# 4-USB-A.net
KiCad netlist of a schematic drawn in Altium Designer
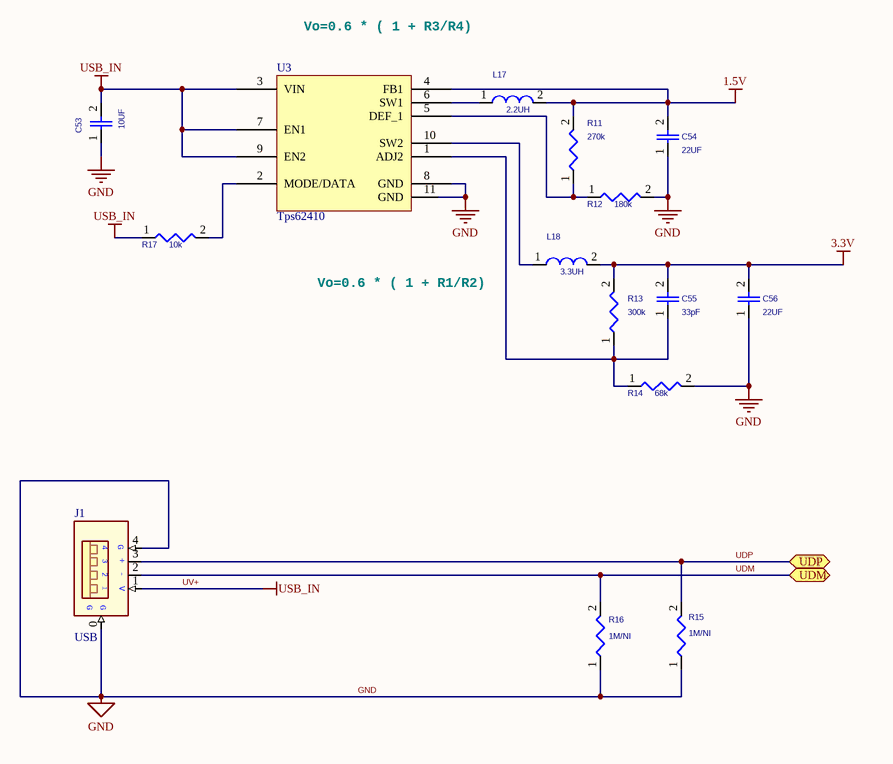
[diagram p0: 4-USB-A.SchDoc]

(export (version "E")
  (design (tool "Eeschema 10.0.6"))
  (components
    (comp (ref "C53") (value "10UF") (footprint "0805") (libsource (lib "*") (part "CAP/0402")))
    (comp (ref "C54") (value "22UF") (footprint "0805") (libsource (lib "*") (part "CAP/0402")))
    (comp (ref "C55") (value "33pF") (footprint "0402") (libsource (lib "*") (part "CAP/0402")))
    (comp (ref "C56") (value "22UF") (footprint "0805") (libsource (lib "*") (part "CAP/0402")))
    (comp (ref "J1") (value "USB") (footprint "USB-A-MALE") (libsource (lib "Euler") (part "USB")))
    (comp (ref "L17") (value "2.2UH") (footprint "0806") (libsource (lib "*") (part "L/2.5*2.0")))
    (comp (ref "L18") (value "3.3UH") (footprint "0806") (libsource (lib "*") (part "L/2.5*2.0")))
    (comp (ref "R11") (value "270k") (footprint "0402") (libsource (lib "*") (part "RES/0402_3")))
    (comp (ref "R12") (value "180k") (footprint "0402") (libsource (lib "*") (part "RES/0402_3")))
    (comp (ref "R13") (value "300k") (footprint "0402") (libsource (lib "*") (part "RES/0402_3")))
    (comp (ref "R14") (value "68k") (footprint "0402") (libsource (lib "*") (part "RES/0402_3")))
    (comp (ref "R15") (value "1M/NI") (footprint "0402") (libsource (lib "*") (part "RES/0402_2")))
    (comp (ref "R16") (value "1M/NI") (footprint "0402") (libsource (lib "*") (part "RES/0402_2")))
    (comp (ref "R17") (value "10k") (libsource (lib "*") (part "RES/0402_3")))
    (comp (ref "U3") (value "Tps62410") (footprint "DFN-10P-3X3") (libsource (lib "Euler") (part "Tps62410")))
  )
  (nets
    (net (code "1") (name "/UDM") (class "Default")
      (node (ref "J1") (pin "2") (pinfunction "D-_2") (pintype "tri_state"))
      (node (ref "R16") (pin "2") (pinfunction "2_2") (pintype "passive"))
    )
    (net (code "2") (name "/UDP") (class "Default")
      (node (ref "J1") (pin "3") (pinfunction "D+_3") (pintype "tri_state"))
      (node (ref "R15") (pin "2") (pinfunction "2_2") (pintype "passive"))
    )
    (net (code "3") (name "1.5V") (class "Default")
      (node (ref "C54") (pin "2") (pinfunction "2_2") (pintype "passive"))
      (node (ref "L17") (pin "2") (pinfunction "2_2") (pintype "passive"))
      (node (ref "R11") (pin "2") (pinfunction "2_2") (pintype "passive"))
      (node (ref "U3") (pin "4") (pinfunction "FB1_4") (pintype "passive"))
    )
    (net (code "4") (name "3.3V") (class "Default")
      (node (ref "C55") (pin "2") (pinfunction "2_2") (pintype "passive"))
      (node (ref "C56") (pin "2") (pinfunction "2_2") (pintype "passive"))
      (node (ref "L18") (pin "2") (pinfunction "2_2") (pintype "passive"))
      (node (ref "R13") (pin "2") (pinfunction "2_2") (pintype "passive"))
    )
    (net (code "5") (name "GND") (class "Default")
      (node (ref "C53") (pin "1") (pinfunction "1_1") (pintype "passive"))
      (node (ref "C54") (pin "1") (pinfunction "1_1") (pintype "passive"))
      (node (ref "C56") (pin "1") (pinfunction "1_1") (pintype "passive"))
      (node (ref "J1") (pin "0") (pinfunction "G_0") (pintype "input"))
      (node (ref "J1") (pin "4") (pinfunction "G_4") (pintype "input"))
      (node (ref "R12") (pin "2") (pinfunction "2_2") (pintype "passive"))
      (node (ref "R14") (pin "2") (pinfunction "2_2") (pintype "passive"))
      (node (ref "R15") (pin "1") (pinfunction "1_1") (pintype "passive"))
      (node (ref "R16") (pin "1") (pinfunction "1_1") (pintype "passive"))
      (node (ref "U3") (pin "11") (pinfunction "GND_11") (pintype "passive"))
      (node (ref "U3") (pin "8") (pinfunction "GND_8") (pintype "passive"))
    )
    (net (code "6") (name "Net-(U3-ADJ2)") (class "Default")
      (node (ref "C55") (pin "1") (pinfunction "1_1") (pintype "passive"))
      (node (ref "R13") (pin "1") (pinfunction "1_1") (pintype "passive"))
      (node (ref "R14") (pin "1") (pinfunction "1_1") (pintype "passive"))
      (node (ref "U3") (pin "1") (pinfunction "ADJ2_1") (pintype "passive"))
    )
    (net (code "7") (name "Net-(U3-DEF_1)") (class "Default")
      (node (ref "R11") (pin "1") (pinfunction "1_1") (pintype "passive"))
      (node (ref "R12") (pin "1") (pinfunction "1_1") (pintype "passive"))
      (node (ref "U3") (pin "5") (pinfunction "DEF_1_5") (pintype "passive"))
    )
    (net (code "8") (name "Net-(U3-MODE{slash}DATA)") (class "Default")
      (node (ref "R17") (pin "2") (pinfunction "2_2") (pintype "passive"))
      (node (ref "U3") (pin "2") (pinfunction "MODE/DATA_2") (pintype "passive"))
    )
    (net (code "9") (name "Net-(U3-SW1)") (class "Default")
      (node (ref "L17") (pin "1") (pinfunction "1_1") (pintype "passive"))
      (node (ref "U3") (pin "6") (pinfunction "SW1_6") (pintype "passive"))
    )
    (net (code "10") (name "Net-(U3-SW2)") (class "Default")
      (node (ref "L18") (pin "1") (pinfunction "1_1") (pintype "passive"))
      (node (ref "U3") (pin "10") (pinfunction "SW2_10") (pintype "passive"))
    )
    (net (code "11") (name "USB_IN") (class "Default")
      (node (ref "C53") (pin "2") (pinfunction "2_2") (pintype "passive"))
      (node (ref "J1") (pin "1") (pinfunction "V+_1") (pintype "input"))
      (node (ref "R17") (pin "1") (pinfunction "1_1") (pintype "passive"))
      (node (ref "U3") (pin "3") (pinfunction "VIN_3") (pintype "passive"))
      (node (ref "U3") (pin "7") (pinfunction "EN1_7") (pintype "passive"))
      (node (ref "U3") (pin "9") (pinfunction "EN2_9") (pintype "passive"))
    )
  )
)
